# SCH_Trail-Camera_2024-05-14.net
KiCad netlist of a schematic drawn in EasyEDA
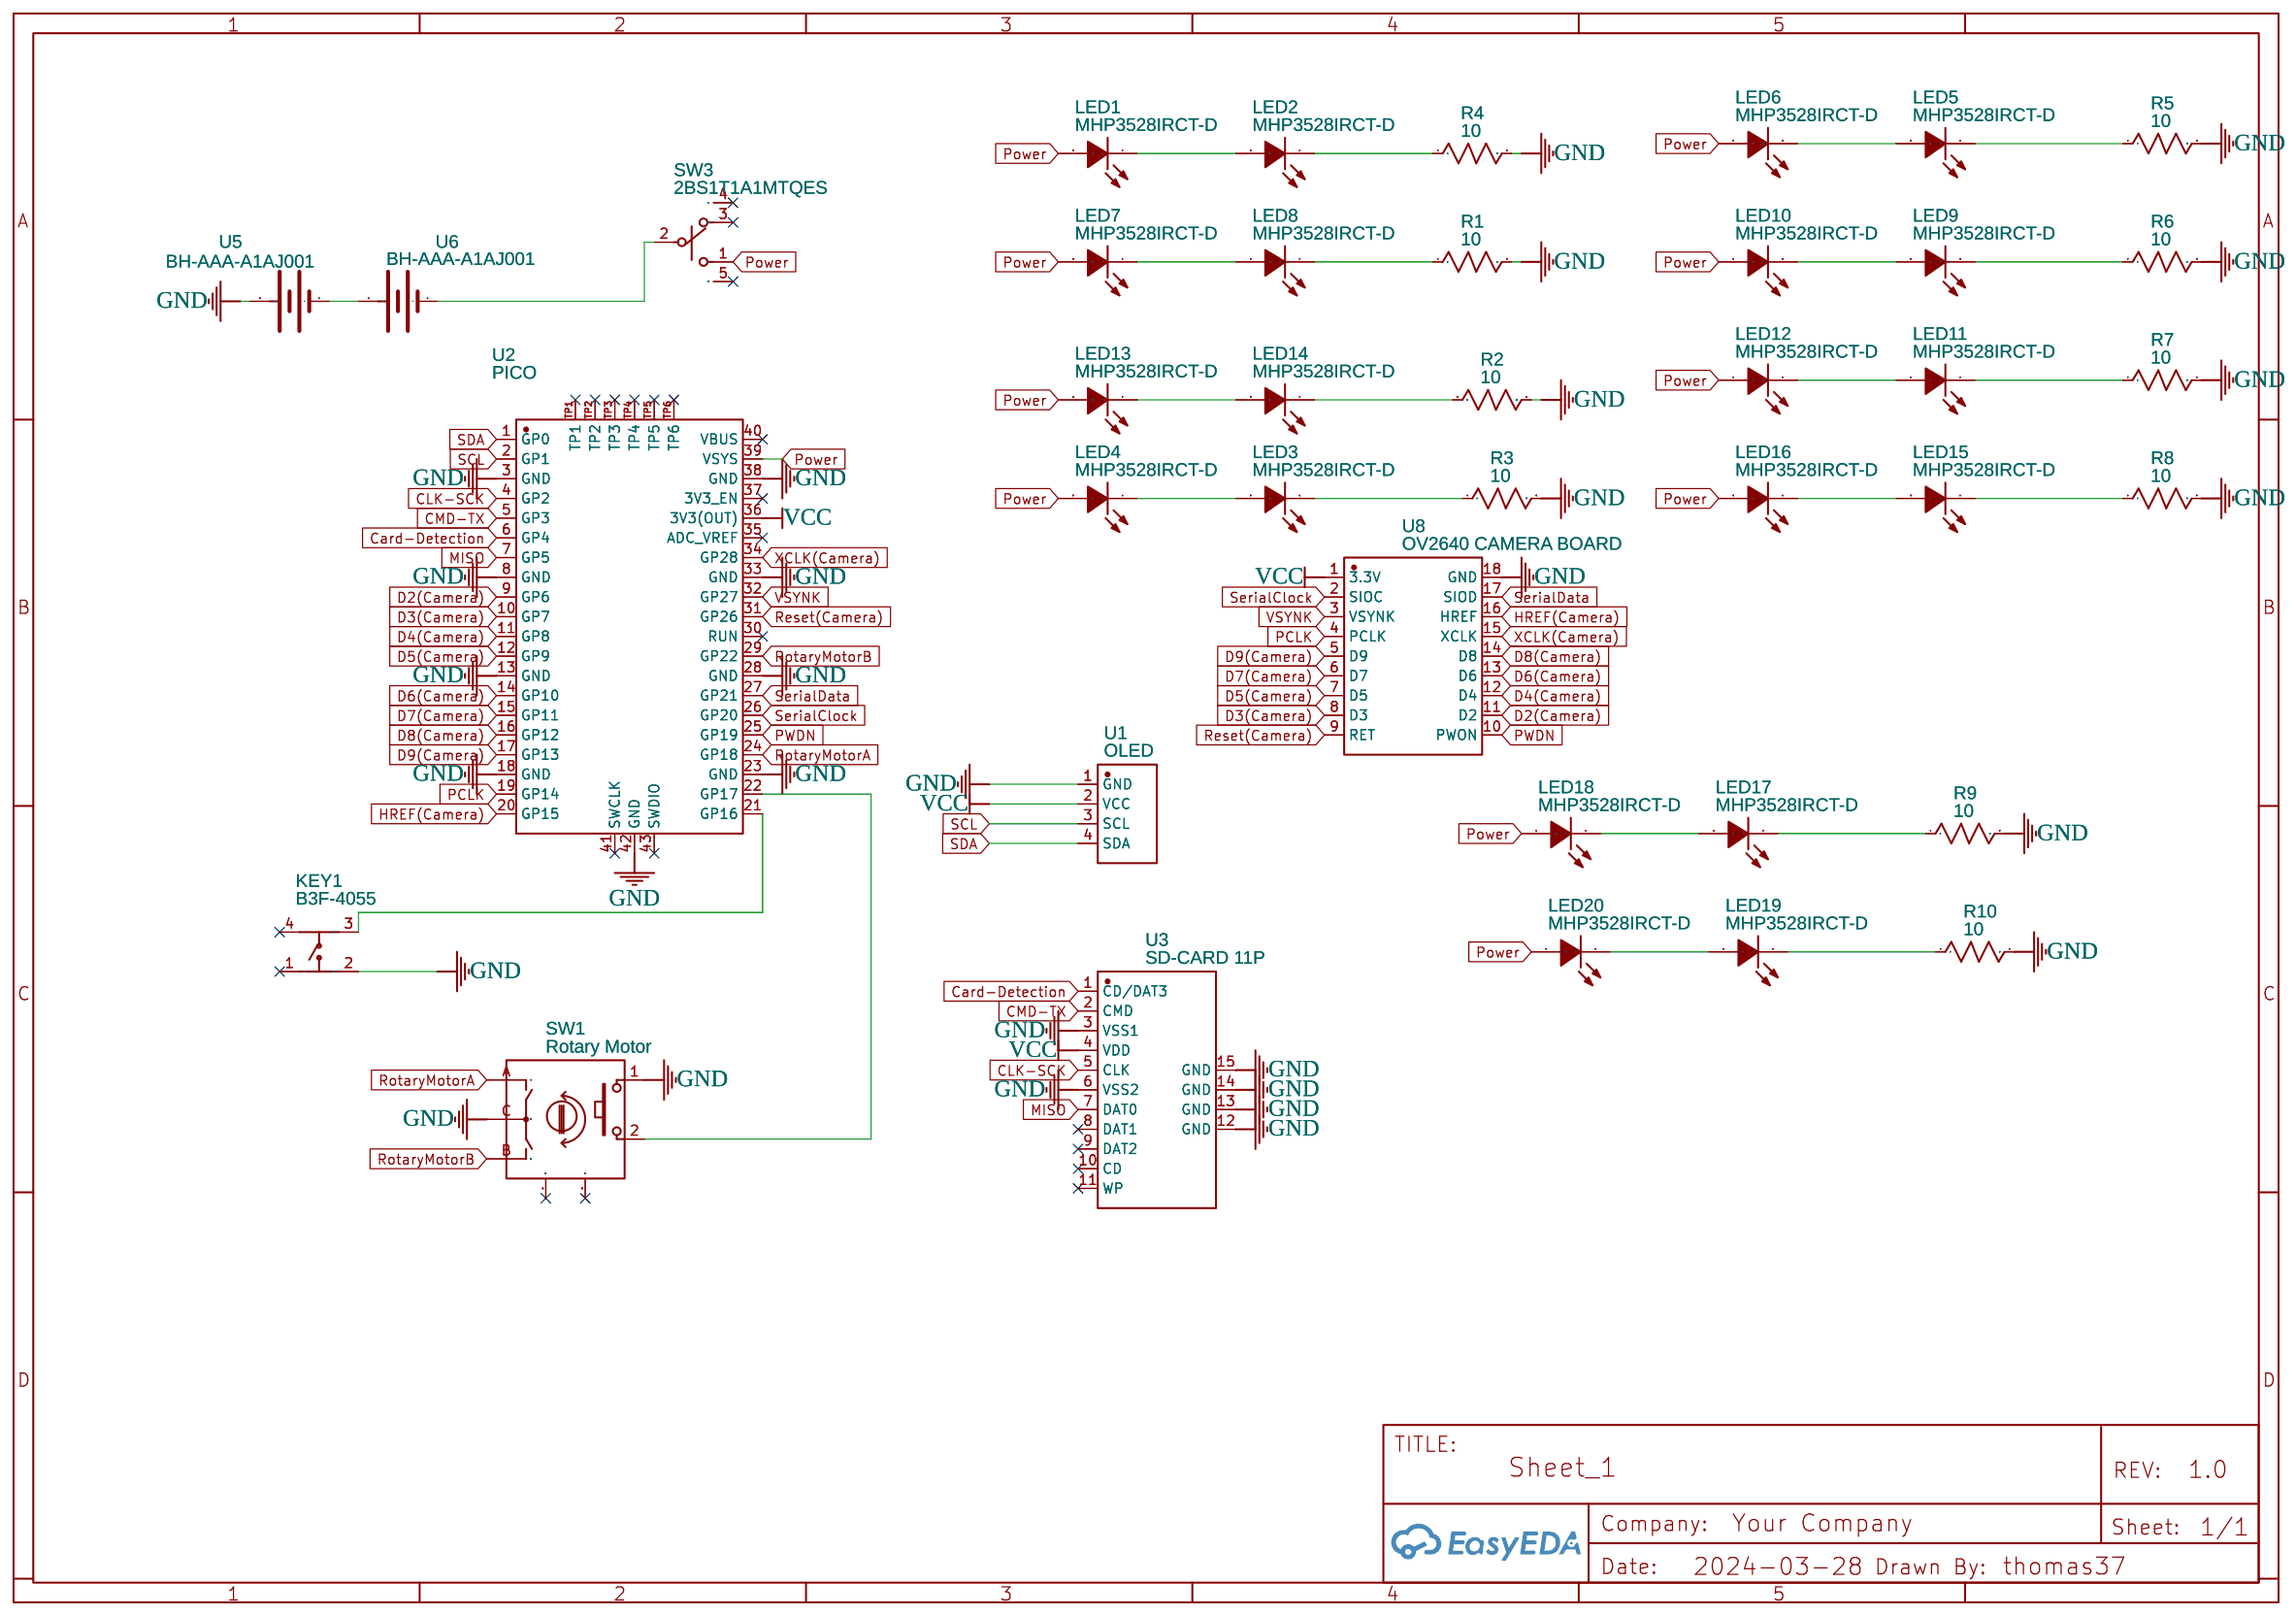
[diagram p0: schematic sheet]

(export (version "E")
  (design (tool "Eeschema 10.0.6"))
  (components
    (comp (ref "KEY1")
      (value "B3F-4055")
      (fields (field (name "Manufacturer") "OMRON(欧姆龙)"))
      (libsource (lib "") (part "B3F-4055"))
    )
    (comp (ref "LED1")
      (value "MHP3528IRCT-D")
      (fields (field (name "Manufacturer") "MEIHUA(美华)"))
      (libsource (lib "") (part "MHP3528IRCT-D"))
    )
    (comp (ref "LED2")
      (value "MHP3528IRCT-D")
      (fields (field (name "Manufacturer") "MEIHUA(美华)"))
      (libsource (lib "") (part "MHP3528IRCT-D"))
    )
    (comp (ref "LED3")
      (value "MHP3528IRCT-D")
      (fields (field (name "Manufacturer") "MEIHUA(美华)"))
      (libsource (lib "") (part "MHP3528IRCT-D"))
    )
    (comp (ref "LED4")
      (value "MHP3528IRCT-D")
      (fields (field (name "Manufacturer") "MEIHUA(美华)"))
      (libsource (lib "") (part "MHP3528IRCT-D"))
    )
    (comp (ref "LED5")
      (value "MHP3528IRCT-D")
      (fields (field (name "Manufacturer") "MEIHUA(美华)"))
      (libsource (lib "") (part "MHP3528IRCT-D"))
    )
    (comp (ref "LED6")
      (value "MHP3528IRCT-D")
      (fields (field (name "Manufacturer") "MEIHUA(美华)"))
      (libsource (lib "") (part "MHP3528IRCT-D"))
    )
    (comp (ref "LED7")
      (value "MHP3528IRCT-D")
      (fields (field (name "Manufacturer") "MEIHUA(美华)"))
      (libsource (lib "") (part "MHP3528IRCT-D"))
    )
    (comp (ref "LED8")
      (value "MHP3528IRCT-D")
      (fields (field (name "Manufacturer") "MEIHUA(美华)"))
      (libsource (lib "") (part "MHP3528IRCT-D"))
    )
    (comp (ref "LED9")
      (value "MHP3528IRCT-D")
      (fields (field (name "Manufacturer") "MEIHUA(美华)"))
      (libsource (lib "") (part "MHP3528IRCT-D"))
    )
    (comp (ref "LED10")
      (value "MHP3528IRCT-D")
      (fields (field (name "Manufacturer") "MEIHUA(美华)"))
      (libsource (lib "") (part "MHP3528IRCT-D"))
    )
    (comp (ref "LED11")
      (value "MHP3528IRCT-D")
      (fields (field (name "Manufacturer") "MEIHUA(美华)"))
      (libsource (lib "") (part "MHP3528IRCT-D"))
    )
    (comp (ref "LED12")
      (value "MHP3528IRCT-D")
      (fields (field (name "Manufacturer") "MEIHUA(美华)"))
      (libsource (lib "") (part "MHP3528IRCT-D"))
    )
    (comp (ref "LED13")
      (value "MHP3528IRCT-D")
      (fields (field (name "Manufacturer") "MEIHUA(美华)"))
      (libsource (lib "") (part "MHP3528IRCT-D"))
    )
    (comp (ref "LED14")
      (value "MHP3528IRCT-D")
      (fields (field (name "Manufacturer") "MEIHUA(美华)"))
      (libsource (lib "") (part "MHP3528IRCT-D"))
    )
    (comp (ref "LED15")
      (value "MHP3528IRCT-D")
      (fields (field (name "Manufacturer") "MEIHUA(美华)"))
      (libsource (lib "") (part "MHP3528IRCT-D"))
    )
    (comp (ref "LED16")
      (value "MHP3528IRCT-D")
      (fields (field (name "Manufacturer") "MEIHUA(美华)"))
      (libsource (lib "") (part "MHP3528IRCT-D"))
    )
    (comp (ref "LED17")
      (value "MHP3528IRCT-D")
      (fields (field (name "Manufacturer") "MEIHUA(美华)"))
      (libsource (lib "") (part "MHP3528IRCT-D"))
    )
    (comp (ref "LED18")
      (value "MHP3528IRCT-D")
      (fields (field (name "Manufacturer") "MEIHUA(美华)"))
      (libsource (lib "") (part "MHP3528IRCT-D"))
    )
    (comp (ref "LED19")
      (value "MHP3528IRCT-D")
      (fields (field (name "Manufacturer") "MEIHUA(美华)"))
      (libsource (lib "") (part "MHP3528IRCT-D"))
    )
    (comp (ref "LED20")
      (value "MHP3528IRCT-D")
      (fields (field (name "Manufacturer") "MEIHUA(美华)"))
      (libsource (lib "") (part "MHP3528IRCT-D"))
    )
    (comp (ref "R1") (value "10") (libsource (lib "") (part "R_0603_US")))
    (comp (ref "R2") (value "10") (libsource (lib "") (part "R_0603_US")))
    (comp (ref "R3") (value "10") (libsource (lib "") (part "R_0603_US")))
    (comp (ref "R4") (value "10") (libsource (lib "") (part "R_0603_US")))
    (comp (ref "R5") (value "10") (libsource (lib "") (part "R_0603_US")))
    (comp (ref "R6") (value "10") (libsource (lib "") (part "R_0603_US")))
    (comp (ref "R7") (value "10") (libsource (lib "") (part "R_0603_US")))
    (comp (ref "R8") (value "10") (libsource (lib "") (part "R_0603_US")))
    (comp (ref "R9") (value "10") (libsource (lib "") (part "R_0603_US")))
    (comp (ref "R10") (value "10") (libsource (lib "") (part "R_0603_US")))
    (comp (ref "SW1")
      (value "Rotary Motor")
      (fields (field (name "Manufacturer Part") "PEC11R-4015F-S0024") (field (name "Manufacturer") "BOURNS"))
      (libsource (lib "") (part "PEC11R-4015F-S0024"))
    )
    (comp (ref "SW3")
      (value "2BS1T1A1MTQES")
      (fields (field (name "Manufacturer") "Dailywell(德利威)"))
      (libsource (lib "") (part "2BS1T1A1MTQES"))
    )
    (comp (ref "U1")
      (value "OLED")
      (fields (field (name "Manufacturer Part") "HS96L03W2C03") (field (name "Manufacturer") "HS(汉昇)"))
      (libsource (lib "") (part "HS96L03W2C03"))
    )
    (comp (ref "U2")
      (value "PICO")
      (fields (field (name "Manufacturer") "Raspberry Pi(树莓派)"))
      (libsource (lib "") (part "PICO"))
    )
    (comp (ref "U3")
      (value "SD-CARD 11P")
      (fields (field (name "Manufacturer") "SHOU HAN(首韩)"))
      (libsource (lib "") (part "SD-CARD 11P"))
    )
    (comp (ref "U5")
      (value "BH-AAA-A1AJ001")
      (fields (field (name "Manufacturer") "MYOUNG(美阳)"))
      (libsource (lib "") (part "BH-AAA-A1AJ001"))
    )
    (comp (ref "U6")
      (value "BH-AAA-A1AJ001")
      (fields (field (name "Manufacturer") "MYOUNG(美阳)"))
      (libsource (lib "") (part "BH-AAA-A1AJ001"))
    )
    (comp (ref "U8")
      (value "OV2640 CAMERA BOARD")
      (fields
        (field (name "Manufacturer Part") "OV2640 Camera Board")
        (field (name "Manufacturer") "Waveshare(微雪电子)")
      )
      (libsource (lib "") (part "OV2640 CAMERA BOARD"))
    )
  )
  (nets
    (net (code "1") (name "CLK-SCK") (class "Default")
      (node (ref "U2") (pin "4") (pinfunction "GP2_4") (pintype "unspecified"))
      (node (ref "U3") (pin "5") (pinfunction "CLK_5") (pintype "unspecified"))
    )
    (net (code "2") (name "CMD-TX") (class "Default")
      (node (ref "U2") (pin "5") (pinfunction "GP3_5") (pintype "unspecified"))
      (node (ref "U3") (pin "2") (pinfunction "CMD_2") (pintype "unspecified"))
    )
    (net (code "3") (name "Card-Detection") (class "Default")
      (node (ref "U2") (pin "6") (pinfunction "GP4_6") (pintype "unspecified"))
      (node (ref "U3") (pin "1") (pinfunction "CD/DAT3_1") (pintype "unspecified"))
    )
    (net (code "4") (name "D2(Camera)") (class "Default")
      (node (ref "U2") (pin "9") (pinfunction "GP6_9") (pintype "unspecified"))
      (node (ref "U8") (pin "11") (pinfunction "D2_11") (pintype "unspecified"))
    )
    (net (code "5") (name "D3(Camera)") (class "Default")
      (node (ref "U2") (pin "10") (pinfunction "GP7_10") (pintype "unspecified"))
      (node (ref "U8") (pin "8") (pinfunction "D3_8") (pintype "unspecified"))
    )
    (net (code "6") (name "D4(Camera)") (class "Default")
      (node (ref "U2") (pin "11") (pinfunction "GP8_11") (pintype "unspecified"))
      (node (ref "U8") (pin "12") (pinfunction "D4_12") (pintype "unspecified"))
    )
    (net (code "7") (name "D5(Camera)") (class "Default")
      (node (ref "U2") (pin "12") (pinfunction "GP9_12") (pintype "unspecified"))
      (node (ref "U8") (pin "7") (pinfunction "D5_7") (pintype "unspecified"))
    )
    (net (code "8") (name "D6(Camera)") (class "Default")
      (node (ref "U2") (pin "14") (pinfunction "GP10_14") (pintype "unspecified"))
      (node (ref "U8") (pin "13") (pinfunction "D6_13") (pintype "unspecified"))
    )
    (net (code "9") (name "D7(Camera)") (class "Default")
      (node (ref "U2") (pin "15") (pinfunction "GP11_15") (pintype "unspecified"))
      (node (ref "U8") (pin "6") (pinfunction "D7_6") (pintype "unspecified"))
    )
    (net (code "10") (name "D8(Camera)") (class "Default")
      (node (ref "U2") (pin "16") (pinfunction "GP12_16") (pintype "unspecified"))
      (node (ref "U8") (pin "14") (pinfunction "D8_14") (pintype "unspecified"))
    )
    (net (code "11") (name "D9(Camera)") (class "Default")
      (node (ref "U2") (pin "17") (pinfunction "GP13_17") (pintype "unspecified"))
      (node (ref "U8") (pin "5") (pinfunction "D9_5") (pintype "unspecified"))
    )
    (net (code "12") (name "GND") (class "Default")
      (node (ref "KEY1") (pin "2") (pinfunction "2_2") (pintype "unspecified"))
      (node (ref "R1") (pin "2") (pinfunction "2_2") (pintype "unspecified"))
      (node (ref "R10") (pin "2") (pinfunction "2_2") (pintype "unspecified"))
      (node (ref "R2") (pin "2") (pinfunction "2_2") (pintype "unspecified"))
      (node (ref "R3") (pin "2") (pinfunction "2_2") (pintype "unspecified"))
      (node (ref "R4") (pin "2") (pinfunction "2_2") (pintype "unspecified"))
      (node (ref "R5") (pin "2") (pinfunction "2_2") (pintype "unspecified"))
      (node (ref "R6") (pin "2") (pinfunction "2_2") (pintype "unspecified"))
      (node (ref "R7") (pin "2") (pinfunction "2_2") (pintype "unspecified"))
      (node (ref "R8") (pin "2") (pinfunction "2_2") (pintype "unspecified"))
      (node (ref "R9") (pin "2") (pinfunction "2_2") (pintype "unspecified"))
      (node (ref "SW1") (pin "1") (pinfunction "1_1") (pintype "unspecified"))
      (node (ref "SW1") (pin "C") (pinfunction "C_C") (pintype "unspecified"))
      (node (ref "U1") (pin "1") (pinfunction "GND_1") (pintype "unspecified"))
      (node (ref "U2") (pin "13") (pinfunction "GND_13") (pintype "unspecified"))
      (node (ref "U2") (pin "18") (pinfunction "GND_18") (pintype "unspecified"))
      (node (ref "U2") (pin "23") (pinfunction "GND_23") (pintype "unspecified"))
      (node (ref "U2") (pin "28") (pinfunction "GND_28") (pintype "unspecified"))
      (node (ref "U2") (pin "3") (pinfunction "GND_3") (pintype "unspecified"))
      (node (ref "U2") (pin "33") (pinfunction "GND_33") (pintype "unspecified"))
      (node (ref "U2") (pin "38") (pinfunction "GND_38") (pintype "unspecified"))
      (node (ref "U2") (pin "42") (pinfunction "GND_42") (pintype "unspecified"))
      (node (ref "U2") (pin "8") (pinfunction "GND_8") (pintype "unspecified"))
      (node (ref "U3") (pin "12") (pinfunction "GND_12") (pintype "unspecified"))
      (node (ref "U3") (pin "13") (pinfunction "GND_13") (pintype "unspecified"))
      (node (ref "U3") (pin "14") (pinfunction "GND_14") (pintype "unspecified"))
      (node (ref "U3") (pin "15") (pinfunction "GND_15") (pintype "unspecified"))
      (node (ref "U3") (pin "3") (pinfunction "VSS1_3") (pintype "unspecified"))
      (node (ref "U3") (pin "6") (pinfunction "VSS2_6") (pintype "unspecified"))
      (node (ref "U5") (pin "2") (pinfunction "+_2") (pintype "passive"))
      (node (ref "U8") (pin "18") (pinfunction "GND_18") (pintype "unspecified"))
    )
    (net (code "13") (name "HREF(Camera)") (class "Default")
      (node (ref "U2") (pin "20") (pinfunction "GP15_20") (pintype "unspecified"))
      (node (ref "U8") (pin "16") (pinfunction "HREF_16") (pintype "unspecified"))
    )
    (net (code "14") (name "MISO") (class "Default")
      (node (ref "U2") (pin "7") (pinfunction "GP5_7") (pintype "unspecified"))
      (node (ref "U3") (pin "7") (pinfunction "DAT0_7") (pintype "unspecified"))
    )
    (net (code "15") (name "Net-(LED1--)") (class "Default")
      (node (ref "LED1") (pin "1") (pinfunction "-_1") (pintype "unspecified"))
      (node (ref "LED2") (pin "2") (pinfunction "+_2") (pintype "unspecified"))
    )
    (net (code "16") (name "Net-(LED2--)") (class "Default")
      (node (ref "LED2") (pin "1") (pinfunction "-_1") (pintype "unspecified"))
      (node (ref "R4") (pin "1") (pinfunction "1_1") (pintype "unspecified"))
    )
    (net (code "17") (name "Net-(LED3-+)") (class "Default")
      (node (ref "LED3") (pin "2") (pinfunction "+_2") (pintype "unspecified"))
      (node (ref "LED4") (pin "1") (pinfunction "-_1") (pintype "unspecified"))
    )
    (net (code "18") (name "Net-(LED3--)") (class "Default")
      (node (ref "LED3") (pin "1") (pinfunction "-_1") (pintype "unspecified"))
      (node (ref "R3") (pin "1") (pinfunction "1_1") (pintype "unspecified"))
    )
    (net (code "19") (name "Net-(LED5-+)") (class "Default")
      (node (ref "LED5") (pin "2") (pinfunction "+_2") (pintype "unspecified"))
      (node (ref "LED6") (pin "1") (pinfunction "-_1") (pintype "unspecified"))
    )
    (net (code "20") (name "Net-(LED5--)") (class "Default")
      (node (ref "LED5") (pin "1") (pinfunction "-_1") (pintype "unspecified"))
      (node (ref "R5") (pin "1") (pinfunction "1_1") (pintype "unspecified"))
    )
    (net (code "21") (name "Net-(LED7--)") (class "Default")
      (node (ref "LED7") (pin "1") (pinfunction "-_1") (pintype "unspecified"))
      (node (ref "LED8") (pin "2") (pinfunction "+_2") (pintype "unspecified"))
    )
    (net (code "22") (name "Net-(LED8--)") (class "Default")
      (node (ref "LED8") (pin "1") (pinfunction "-_1") (pintype "unspecified"))
      (node (ref "R1") (pin "1") (pinfunction "1_1") (pintype "unspecified"))
    )
    (net (code "23") (name "Net-(LED9--)") (class "Default")
      (node (ref "LED9") (pin "1") (pinfunction "-_1") (pintype "unspecified"))
      (node (ref "R6") (pin "1") (pinfunction "1_1") (pintype "unspecified"))
    )
    (net (code "24") (name "Net-(LED10--)") (class "Default")
      (node (ref "LED10") (pin "1") (pinfunction "-_1") (pintype "unspecified"))
      (node (ref "LED9") (pin "2") (pinfunction "+_2") (pintype "unspecified"))
    )
    (net (code "25") (name "Net-(LED11-+)") (class "Default")
      (node (ref "LED11") (pin "2") (pinfunction "+_2") (pintype "unspecified"))
      (node (ref "LED12") (pin "1") (pinfunction "-_1") (pintype "unspecified"))
    )
    (net (code "26") (name "Net-(LED11--)") (class "Default")
      (node (ref "LED11") (pin "1") (pinfunction "-_1") (pintype "unspecified"))
      (node (ref "R7") (pin "1") (pinfunction "1_1") (pintype "unspecified"))
    )
    (net (code "27") (name "Net-(LED13--)") (class "Default")
      (node (ref "LED13") (pin "1") (pinfunction "-_1") (pintype "unspecified"))
      (node (ref "LED14") (pin "2") (pinfunction "+_2") (pintype "unspecified"))
    )
    (net (code "28") (name "Net-(LED14--)") (class "Default")
      (node (ref "LED14") (pin "1") (pinfunction "-_1") (pintype "unspecified"))
      (node (ref "R2") (pin "1") (pinfunction "1_1") (pintype "unspecified"))
    )
    (net (code "29") (name "Net-(LED15-+)") (class "Default")
      (node (ref "LED15") (pin "2") (pinfunction "+_2") (pintype "unspecified"))
      (node (ref "LED16") (pin "1") (pinfunction "-_1") (pintype "unspecified"))
    )
    (net (code "30") (name "Net-(LED15--)") (class "Default")
      (node (ref "LED15") (pin "1") (pinfunction "-_1") (pintype "unspecified"))
      (node (ref "R8") (pin "1") (pinfunction "1_1") (pintype "unspecified"))
    )
    (net (code "31") (name "Net-(LED17-+)") (class "Default")
      (node (ref "LED17") (pin "2") (pinfunction "+_2") (pintype "unspecified"))
      (node (ref "LED18") (pin "1") (pinfunction "-_1") (pintype "unspecified"))
    )
    (net (code "32") (name "Net-(LED17--)") (class "Default")
      (node (ref "LED17") (pin "1") (pinfunction "-_1") (pintype "unspecified"))
      (node (ref "R9") (pin "1") (pinfunction "1_1") (pintype "unspecified"))
    )
    (net (code "33") (name "Net-(LED19-+)") (class "Default")
      (node (ref "LED19") (pin "2") (pinfunction "+_2") (pintype "unspecified"))
      (node (ref "LED20") (pin "1") (pinfunction "-_1") (pintype "unspecified"))
    )
    (net (code "34") (name "Net-(LED19--)") (class "Default")
      (node (ref "LED19") (pin "1") (pinfunction "-_1") (pintype "unspecified"))
      (node (ref "R10") (pin "1") (pinfunction "1_1") (pintype "unspecified"))
    )
    (net (code "35") (name "Net-(U2-GP16)") (class "Default")
      (node (ref "KEY1") (pin "3") (pinfunction "3_3") (pintype "unspecified"))
      (node (ref "U2") (pin "21") (pinfunction "GP16_21") (pintype "unspecified"))
    )
    (net (code "36") (name "Net-(U2-GP17)") (class "Default")
      (node (ref "SW1") (pin "2") (pinfunction "2_2") (pintype "unspecified"))
      (node (ref "U2") (pin "22") (pinfunction "GP17_22") (pintype "unspecified"))
    )
    (net (code "37") (name "Net-(U5--)") (class "Default")
      (node (ref "U5") (pin "1") (pinfunction "-_1") (pintype "passive"))
      (node (ref "U6") (pin "2") (pinfunction "+_2") (pintype "passive"))
    )
    (net (code "38") (name "Net-(U6--)") (class "Default")
      (node (ref "SW3") (pin "2") (pinfunction "2_2") (pintype "unspecified"))
      (node (ref "U6") (pin "1") (pinfunction "-_1") (pintype "passive"))
    )
    (net (code "39") (name "PCLK") (class "Default")
      (node (ref "U2") (pin "19") (pinfunction "GP14_19") (pintype "unspecified"))
      (node (ref "U8") (pin "4") (pinfunction "PCLK_4") (pintype "unspecified"))
    )
    (net (code "40") (name "PWDN") (class "Default")
      (node (ref "U2") (pin "25") (pinfunction "GP19_25") (pintype "unspecified"))
      (node (ref "U8") (pin "10") (pinfunction "PWON_10") (pintype "unspecified"))
    )
    (net (code "41") (name "Power") (class "Default")
      (node (ref "LED1") (pin "2") (pinfunction "+_2") (pintype "unspecified"))
      (node (ref "LED10") (pin "2") (pinfunction "+_2") (pintype "unspecified"))
      (node (ref "LED12") (pin "2") (pinfunction "+_2") (pintype "unspecified"))
      (node (ref "LED13") (pin "2") (pinfunction "+_2") (pintype "unspecified"))
      (node (ref "LED16") (pin "2") (pinfunction "+_2") (pintype "unspecified"))
      (node (ref "LED18") (pin "2") (pinfunction "+_2") (pintype "unspecified"))
      (node (ref "LED20") (pin "2") (pinfunction "+_2") (pintype "unspecified"))
      (node (ref "LED4") (pin "2") (pinfunction "+_2") (pintype "unspecified"))
      (node (ref "LED6") (pin "2") (pinfunction "+_2") (pintype "unspecified"))
      (node (ref "LED7") (pin "2") (pinfunction "+_2") (pintype "unspecified"))
      (node (ref "SW3") (pin "1") (pinfunction "1_1") (pintype "unspecified"))
      (node (ref "U2") (pin "39") (pinfunction "VSYS_39") (pintype "unspecified"))
    )
    (net (code "42") (name "Reset(Camera)") (class "Default")
      (node (ref "U2") (pin "31") (pinfunction "GP26_31") (pintype "unspecified"))
      (node (ref "U8") (pin "9") (pinfunction "RET_9") (pintype "unspecified"))
    )
    (net (code "43") (name "RotaryMotorA") (class "Default")
      (node (ref "SW1") (pin "A") (pinfunction "A_A") (pintype "unspecified"))
      (node (ref "U2") (pin "24") (pinfunction "GP18_24") (pintype "unspecified"))
    )
    (net (code "44") (name "RotaryMotorB") (class "Default")
      (node (ref "SW1") (pin "B") (pinfunction "B_B") (pintype "unspecified"))
      (node (ref "U2") (pin "29") (pinfunction "GP22_29") (pintype "unspecified"))
    )
    (net (code "45") (name "SCL") (class "Default")
      (node (ref "U1") (pin "3") (pinfunction "SCL_3") (pintype "unspecified"))
      (node (ref "U2") (pin "2") (pinfunction "GP1_2") (pintype "unspecified"))
    )
    (net (code "46") (name "SDA") (class "Default")
      (node (ref "U1") (pin "4") (pinfunction "SDA_4") (pintype "unspecified"))
      (node (ref "U2") (pin "1") (pinfunction "GP0_1") (pintype "unspecified"))
    )
    (net (code "47") (name "SerialClock") (class "Default")
      (node (ref "U2") (pin "26") (pinfunction "GP20_26") (pintype "unspecified"))
      (node (ref "U8") (pin "2") (pinfunction "SIOC_2") (pintype "unspecified"))
    )
    (net (code "48") (name "SerialData") (class "Default")
      (node (ref "U2") (pin "27") (pinfunction "GP21_27") (pintype "unspecified"))
      (node (ref "U8") (pin "17") (pinfunction "SIOD_17") (pintype "unspecified"))
    )
    (net (code "49") (name "VCC") (class "Default")
      (node (ref "U1") (pin "2") (pinfunction "VCC_2") (pintype "unspecified"))
      (node (ref "U2") (pin "36") (pinfunction "3V3(OUT)_36") (pintype "unspecified"))
      (node (ref "U3") (pin "4") (pinfunction "VDD_4") (pintype "unspecified"))
      (node (ref "U8") (pin "1") (pinfunction "3.3V_1") (pintype "unspecified"))
    )
    (net (code "50") (name "VSYNK") (class "Default")
      (node (ref "U2") (pin "32") (pinfunction "GP27_32") (pintype "unspecified"))
      (node (ref "U8") (pin "3") (pinfunction "VSYNK_3") (pintype "unspecified"))
    )
    (net (code "51") (name "XCLK(Camera)") (class "Default")
      (node (ref "U2") (pin "34") (pinfunction "GP28_34") (pintype "unspecified"))
      (node (ref "U8") (pin "15") (pinfunction "XCLK_15") (pintype "unspecified"))
    )
    (net (code "52") (name "unconnected-(KEY1-Pad1)") (class "Default")
      (node (ref "KEY1") (pin "1") (pinfunction "1_1") (pintype "unspecified+no_connect"))
    )
    (net (code "53") (name "unconnected-(KEY1-Pad4)") (class "Default")
      (node (ref "KEY1") (pin "4") (pinfunction "4_4") (pintype "unspecified+no_connect"))
    )
    (net (code "54") (name "unconnected-(SW1-PadMT1)") (class "Default")
      (node (ref "SW1") (pin "MT1") (pinfunction "MT1_MT1") (pintype "unspecified+no_connect"))
    )
    (net (code "55") (name "unconnected-(SW1-PadMT2)") (class "Default")
      (node (ref "SW1") (pin "MT2") (pinfunction "MT2_MT2") (pintype "unspecified+no_connect"))
    )
    (net (code "56") (name "unconnected-(SW3-Pad3)") (class "Default")
      (node (ref "SW3") (pin "3") (pinfunction "3_3") (pintype "unspecified+no_connect"))
    )
    (net (code "57") (name "unconnected-(SW3-Pad4)") (class "Default")
      (node (ref "SW3") (pin "4") (pinfunction "4_4") (pintype "unspecified+no_connect"))
    )
    (net (code "58") (name "unconnected-(SW3-Pad5)") (class "Default")
      (node (ref "SW3") (pin "5") (pinfunction "5_5") (pintype "unspecified+no_connect"))
    )
    (net (code "59") (name "unconnected-(U2-3V3_EN-Pad37)") (class "Default")
      (node (ref "U2") (pin "37") (pinfunction "3V3_EN_37") (pintype "unspecified+no_connect"))
    )
    (net (code "60") (name "unconnected-(U2-ADC_VREF-Pad35)") (class "Default")
      (node (ref "U2") (pin "35") (pinfunction "ADC_VREF_35") (pintype "unspecified+no_connect"))
    )
    (net (code "61") (name "unconnected-(U2-PadTP1)") (class "Default")
      (node (ref "U2") (pin "TP1") (pinfunction "TP1_TP1") (pintype "unspecified+no_connect"))
    )
    (net (code "62") (name "unconnected-(U2-PadTP2)") (class "Default")
      (node (ref "U2") (pin "TP2") (pinfunction "TP2_TP2") (pintype "unspecified+no_connect"))
    )
    (net (code "63") (name "unconnected-(U2-PadTP3)") (class "Default")
      (node (ref "U2") (pin "TP3") (pinfunction "TP3_TP3") (pintype "unspecified+no_connect"))
    )
    (net (code "64") (name "unconnected-(U2-PadTP4)") (class "Default")
      (node (ref "U2") (pin "TP4") (pinfunction "TP4_TP4") (pintype "unspecified+no_connect"))
    )
    (net (code "65") (name "unconnected-(U2-PadTP5)") (class "Default")
      (node (ref "U2") (pin "TP5") (pinfunction "TP5_TP5") (pintype "unspecified+no_connect"))
    )
    (net (code "66") (name "unconnected-(U2-PadTP6)") (class "Default")
      (node (ref "U2") (pin "TP6") (pinfunction "TP6_TP6") (pintype "unspecified+no_connect"))
    )
    (net (code "67") (name "unconnected-(U2-RUN-Pad30)") (class "Default")
      (node (ref "U2") (pin "30") (pinfunction "RUN_30") (pintype "unspecified+no_connect"))
    )
    (net (code "68") (name "unconnected-(U2-SWCLK-Pad41)") (class "Default")
      (node (ref "U2") (pin "41") (pinfunction "SWCLK_41") (pintype "unspecified+no_connect"))
    )
    (net (code "69") (name "unconnected-(U2-SWDIO-Pad43)") (class "Default")
      (node (ref "U2") (pin "43") (pinfunction "SWDIO_43") (pintype "unspecified+no_connect"))
    )
    (net (code "70") (name "unconnected-(U2-VBUS-Pad40)") (class "Default")
      (node (ref "U2") (pin "40") (pinfunction "VBUS_40") (pintype "unspecified+no_connect"))
    )
    (net (code "71") (name "unconnected-(U3-CD-Pad10)") (class "Default")
      (node (ref "U3") (pin "10") (pinfunction "CD_10") (pintype "unspecified+no_connect"))
    )
    (net (code "72") (name "unconnected-(U3-DAT1-Pad8)") (class "Default")
      (node (ref "U3") (pin "8") (pinfunction "DAT1_8") (pintype "unspecified+no_connect"))
    )
    (net (code "73") (name "unconnected-(U3-DAT2-Pad9)") (class "Default")
      (node (ref "U3") (pin "9") (pinfunction "DAT2_9") (pintype "unspecified+no_connect"))
    )
    (net (code "74") (name "unconnected-(U3-WP-Pad11)") (class "Default")
      (node (ref "U3") (pin "11") (pinfunction "WP_11") (pintype "unspecified+no_connect"))
    )
  )
)
